# FIT_HDMI_X16-33.net
KiCad netlist of a schematic drawn in Altium Designer
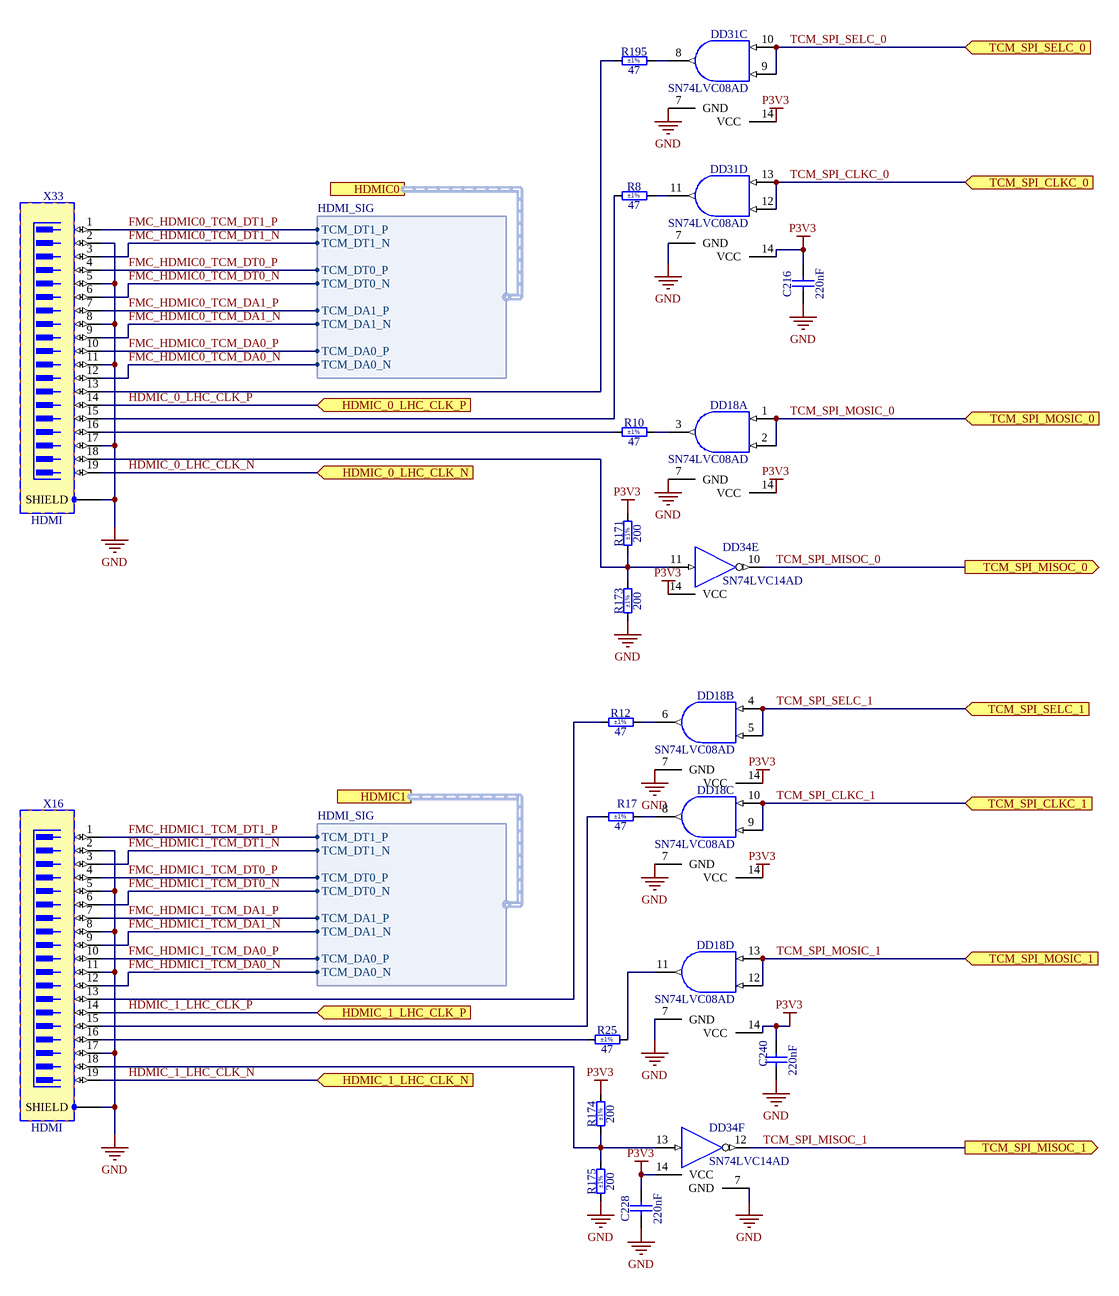
[diagram p0: FIT_HDMI_X16-33.SchDoc]

(export (version "E")
  (design (tool "Eeschema 10.0.6"))
  (components
    (comp (ref "C216")
      (value "220nF")
      (footprint "CAPC2012X135N")
      (description "Non-polarised capacitor")
      (fields
        (field (name "PART NUMBER") "CC0805_220NF_50V_10%_X7R")
        (field (name "VOLTAGE") "50V")
        (field (name "AUTHOR") "CERN DEM JLC")
      )
      (libsource (lib "Capacitors") (part "Capacitor - non polarized"))
    )
    (comp (ref "C228")
      (value "220nF")
      (footprint "CAPC2012X135N")
      (description "Non-polarised capacitor")
      (fields
        (field (name "PART NUMBER") "CC0805_220NF_50V_10%_X7R")
        (field (name "VOLTAGE") "50V")
        (field (name "AUTHOR") "CERN DEM JLC")
      )
      (libsource (lib "Capacitors") (part "Capacitor - non polarized"))
    )
    (comp (ref "C240")
      (value "220nF")
      (footprint "CAPC2012X135N")
      (description "Non-polarised capacitor")
      (fields
        (field (name "PART NUMBER") "CC0805_220NF_50V_10%_X7R")
        (field (name "VOLTAGE") "50V")
        (field (name "AUTHOR") "CERN DEM JLC")
      )
      (libsource (lib "Capacitors") (part "Capacitor - non polarized"))
    )
    (comp (ref "DD18")
      (value "SN74LVC08AD")
      (footprint "SOIC127P600X175-14N")
      (description "Quad 2-Input AND Gate")
      (fields (field (name "MANUFACTURER") "TEXAS INSTRUMENTS") (field (name "AUTHOR") "CERN DEM JLC"))
      (libsource (lib "ICs And Semiconductors") (part "7408"))
    )
    (comp (ref "DD31")
      (value "SN74LVC08AD")
      (footprint "SOIC127P600X175-14N")
      (description "Quad 2-Input AND Gate")
      (fields (field (name "MANUFACTURER") "TEXAS INSTRUMENTS") (field (name "AUTHOR") "CERN DEM JLC"))
      (libsource (lib "ICs And Semiconductors") (part "7408"))
    )
    (comp (ref "DD34")
      (value "SN74LVC14AD")
      (footprint "SOIC127P600X175-14N")
      (description "Hex Schmitt-Trigger Inverter")
      (fields (field (name "MANUFACTURER") "TEXAS INSTRUMENTS") (field (name "AUTHOR") "CERN DEM JMW"))
      (libsource (lib "ICs And Semiconductors") (part "7414"))
    )
    (comp (ref "R8")
      (value "47")
      (footprint "RESC2012X60N")
      (description "Resistor - 1%")
      (fields
        (field (name "TOLERANCE") "±1%")
        (field (name "PART NUMBER") "R0805_47R_1%_0.125W_100PPM")
        (field (name "POWER") "0.125W")
        (field (name "AUTHOR") "CERN DEM JLC")
      )
      (libsource (lib "Resistors") (part "Resistor - 1%"))
    )
    (comp (ref "R10")
      (value "47")
      (footprint "RESC2012X60N")
      (description "Resistor - 1%")
      (fields
        (field (name "TOLERANCE") "±1%")
        (field (name "PART NUMBER") "R0805_47R_1%_0.125W_100PPM")
        (field (name "POWER") "0.125W")
        (field (name "AUTHOR") "CERN DEM JLC")
      )
      (libsource (lib "Resistors") (part "Resistor - 1%"))
    )
    (comp (ref "R12")
      (value "47")
      (footprint "RESC2012X60N")
      (description "Resistor - 1%")
      (fields
        (field (name "TOLERANCE") "±1%")
        (field (name "PART NUMBER") "R0805_47R_1%_0.125W_100PPM")
        (field (name "POWER") "0.125W")
        (field (name "AUTHOR") "CERN DEM JLC")
      )
      (libsource (lib "Resistors") (part "Resistor - 1%"))
    )
    (comp (ref "R17")
      (value "47")
      (footprint "RESC2012X60N")
      (description "Resistor - 1%")
      (fields
        (field (name "TOLERANCE") "±1%")
        (field (name "PART NUMBER") "R0805_47R_1%_0.125W_100PPM")
        (field (name "POWER") "0.125W")
        (field (name "AUTHOR") "CERN DEM JLC")
      )
      (libsource (lib "Resistors") (part "Resistor - 1%"))
    )
    (comp (ref "R25")
      (value "47")
      (footprint "RESC2012X60N")
      (description "Resistor - 1%")
      (fields
        (field (name "TOLERANCE") "±1%")
        (field (name "PART NUMBER") "R0805_47R_1%_0.125W_100PPM")
        (field (name "POWER") "0.125W")
        (field (name "AUTHOR") "CERN DEM JLC")
      )
      (libsource (lib "Resistors") (part "Resistor - 1%"))
    )
    (comp (ref "R171")
      (value "200")
      (footprint "RESC2012X60N")
      (description "Resistor - 1%")
      (fields
        (field (name "TOLERANCE") "±1%")
        (field (name "PART NUMBER") "R0805_200R_1%_0.125W_100PPM")
        (field (name "POWER") "0.125W")
        (field (name "AUTHOR") "CERN DEM JLC")
      )
      (libsource (lib "Resistors") (part "Resistor - 1%"))
    )
    (comp (ref "R173")
      (value "200")
      (footprint "RESC2012X60N")
      (description "Resistor - 1%")
      (fields
        (field (name "TOLERANCE") "±1%")
        (field (name "PART NUMBER") "R0805_200R_1%_0.125W_100PPM")
        (field (name "POWER") "0.125W")
        (field (name "AUTHOR") "CERN DEM JLC")
      )
      (libsource (lib "Resistors") (part "Resistor - 1%"))
    )
    (comp (ref "R174")
      (value "200")
      (footprint "RESC2012X60N")
      (description "Resistor - 1%")
      (fields
        (field (name "TOLERANCE") "±1%")
        (field (name "PART NUMBER") "R0805_200R_1%_0.125W_100PPM")
        (field (name "POWER") "0.125W")
        (field (name "AUTHOR") "CERN DEM JLC")
      )
      (libsource (lib "Resistors") (part "Resistor - 1%"))
    )
    (comp (ref "R175")
      (value "200")
      (footprint "RESC2012X60N")
      (description "Resistor - 1%")
      (fields
        (field (name "TOLERANCE") "±1%")
        (field (name "PART NUMBER") "R0805_200R_1%_0.125W_100PPM")
        (field (name "POWER") "0.125W")
        (field (name "AUTHOR") "CERN DEM JLC")
      )
      (libsource (lib "Resistors") (part "Resistor - 1%"))
    )
    (comp (ref "R195")
      (value "47")
      (footprint "RESC2012X60N")
      (description "Resistor - 1%")
      (fields
        (field (name "TOLERANCE") "±1%")
        (field (name "PART NUMBER") "R0805_47R_1%_0.125W_100PPM")
        (field (name "POWER") "0.125W")
        (field (name "AUTHOR") "CERN DEM JLC")
      )
      (libsource (lib "Resistors") (part "Resistor - 1%"))
    )
    (comp (ref "X16")
      (value "HDMI")
      (footprint "TYCO_2007435-1")
      (description "Connector HDMI 19 Male + 1 Shield")
      (fields
        (field (name "PART NUMBER") "TYCO_2007435-1")
        (field (name "MANUFACTURER") "TYCO ELECTRONICS")
        (field (name "AUTHOR") "CERN DEM MR")
      )
      (libsource (lib "Connectors") (part "Connector HDMI 19 Male + 1 Shield"))
    )
    (comp (ref "X33")
      (value "HDMI")
      (footprint "TYCO_2007435-1")
      (description "Connector HDMI 19 Male + 1 Shield")
      (fields
        (field (name "PART NUMBER") "TYCO_2007435-1")
        (field (name "MANUFACTURER") "TYCO ELECTRONICS")
        (field (name "AUTHOR") "CERN DEM MR")
      )
      (libsource (lib "Connectors") (part "Connector HDMI 19 Male + 1 Shield"))
    )
  )
  (nets
    (net (code "2") (name "/FMC_HDMIC0_TCM_DA0_N") (class "Default")
      (node (ref "X33") (pin "12") (pinfunction "12_12") (pintype "bidirectional"))
    )
    (net (code "3") (name "/FMC_HDMIC0_TCM_DA0_P") (class "Default")
      (node (ref "X33") (pin "10") (pinfunction "10_10") (pintype "bidirectional"))
    )
    (net (code "4") (name "/FMC_HDMIC0_TCM_DA1_N") (class "Default")
      (node (ref "X33") (pin "9") (pinfunction "9_9") (pintype "bidirectional"))
    )
    (net (code "5") (name "/FMC_HDMIC0_TCM_DA1_P") (class "Default")
      (node (ref "X33") (pin "7") (pinfunction "7_7") (pintype "bidirectional"))
    )
    (net (code "6") (name "/FMC_HDMIC0_TCM_DT0_N") (class "Default")
      (node (ref "X33") (pin "6") (pinfunction "6_6") (pintype "bidirectional"))
    )
    (net (code "7") (name "/FMC_HDMIC0_TCM_DT0_P") (class "Default")
      (node (ref "X33") (pin "4") (pinfunction "4_4") (pintype "bidirectional"))
    )
    (net (code "8") (name "/FMC_HDMIC0_TCM_DT1_N") (class "Default")
      (node (ref "X33") (pin "3") (pinfunction "3_3") (pintype "bidirectional"))
    )
    (net (code "9") (name "/FMC_HDMIC0_TCM_DT1_P") (class "Default")
      (node (ref "X33") (pin "1") (pinfunction "1_1") (pintype "bidirectional"))
    )
    (net (code "10") (name "/FMC_HDMIC1_TCM_DA0_N") (class "Default")
      (node (ref "X16") (pin "12") (pinfunction "12_12") (pintype "bidirectional"))
    )
    (net (code "11") (name "/FMC_HDMIC1_TCM_DA0_P") (class "Default")
      (node (ref "X16") (pin "10") (pinfunction "10_10") (pintype "bidirectional"))
    )
    (net (code "12") (name "/FMC_HDMIC1_TCM_DA1_N") (class "Default")
      (node (ref "X16") (pin "9") (pinfunction "9_9") (pintype "bidirectional"))
    )
    (net (code "13") (name "/FMC_HDMIC1_TCM_DA1_P") (class "Default")
      (node (ref "X16") (pin "7") (pinfunction "7_7") (pintype "bidirectional"))
    )
    (net (code "14") (name "/FMC_HDMIC1_TCM_DT0_N") (class "Default")
      (node (ref "X16") (pin "6") (pinfunction "6_6") (pintype "bidirectional"))
    )
    (net (code "15") (name "/FMC_HDMIC1_TCM_DT0_P") (class "Default")
      (node (ref "X16") (pin "4") (pinfunction "4_4") (pintype "bidirectional"))
    )
    (net (code "16") (name "/FMC_HDMIC1_TCM_DT1_N") (class "Default")
      (node (ref "X16") (pin "3") (pinfunction "3_3") (pintype "bidirectional"))
    )
    (net (code "17") (name "/FMC_HDMIC1_TCM_DT1_P") (class "Default")
      (node (ref "X16") (pin "1") (pinfunction "1_1") (pintype "bidirectional"))
    )
    (net (code "18") (name "/HDMIC_0_LHC_CLK_N") (class "Default")
      (node (ref "X33") (pin "19") (pinfunction "19_19") (pintype "bidirectional"))
    )
    (net (code "19") (name "/HDMIC_0_LHC_CLK_P") (class "Default")
      (node (ref "X33") (pin "14") (pinfunction "14_14") (pintype "bidirectional"))
    )
    (net (code "20") (name "/HDMIC_1_LHC_CLK_N") (class "Default")
      (node (ref "X16") (pin "19") (pinfunction "19_19") (pintype "bidirectional"))
    )
    (net (code "21") (name "/HDMIC_1_LHC_CLK_P") (class "Default")
      (node (ref "X16") (pin "14") (pinfunction "14_14") (pintype "bidirectional"))
    )
    (net (code "22") (name "/TCM_SPI_CLKC_0") (class "Default")
      (node (ref "DD31") (pin "12") (pinfunction "B_12") (pintype "input"))
      (node (ref "DD31") (pin "13") (pinfunction "A_13") (pintype "input"))
    )
    (net (code "23") (name "/TCM_SPI_CLKC_1") (class "Default")
      (node (ref "DD18") (pin "10") (pinfunction "A_10") (pintype "input"))
      (node (ref "DD18") (pin "9") (pinfunction "B_9") (pintype "input"))
    )
    (net (code "24") (name "/TCM_SPI_MISOC_0") (class "Default")
      (node (ref "DD34") (pin "10") (pinfunction "OUT_10") (pintype "output"))
    )
    (net (code "25") (name "/TCM_SPI_MISOC_1") (class "Default")
      (node (ref "DD34") (pin "12") (pinfunction "OUT_12") (pintype "output"))
    )
    (net (code "26") (name "/TCM_SPI_MOSIC_0") (class "Default")
      (node (ref "DD18") (pin "1") (pinfunction "A_1") (pintype "input"))
      (node (ref "DD18") (pin "2") (pinfunction "B_2") (pintype "input"))
    )
    (net (code "27") (name "/TCM_SPI_MOSIC_1") (class "Default")
      (node (ref "DD18") (pin "12") (pinfunction "B_12") (pintype "input"))
      (node (ref "DD18") (pin "13") (pinfunction "A_13") (pintype "input"))
    )
    (net (code "28") (name "/TCM_SPI_SELC_0") (class "Default")
      (node (ref "DD31") (pin "10") (pinfunction "A_10") (pintype "input"))
      (node (ref "DD31") (pin "9") (pinfunction "B_9") (pintype "input"))
    )
    (net (code "29") (name "/TCM_SPI_SELC_1") (class "Default")
      (node (ref "DD18") (pin "4") (pinfunction "A_4") (pintype "input"))
      (node (ref "DD18") (pin "5") (pinfunction "B_5") (pintype "input"))
    )
    (net (code "31") (name "GND") (class "Default")
      (node (ref "C216") (pin "1") (pinfunction "1_1") (pintype "passive"))
      (node (ref "C228") (pin "1") (pinfunction "1_1") (pintype "passive"))
      (node (ref "C240") (pin "1") (pinfunction "1_1") (pintype "passive"))
      (node (ref "DD18") (pin "7") (pinfunction "GND_7") (pintype "power_in"))
      (node (ref "DD31") (pin "7") (pinfunction "GND_7") (pintype "power_in"))
      (node (ref "DD34") (pin "7") (pinfunction "GND_7") (pintype "power_in"))
      (node (ref "R173") (pin "1") (pinfunction "1_1") (pintype "passive"))
      (node (ref "R175") (pin "1") (pinfunction "1_1") (pintype "passive"))
      (node (ref "X16") (pin "11") (pinfunction "11_11") (pintype "bidirectional"))
      (node (ref "X16") (pin "17") (pinfunction "17_17") (pintype "bidirectional"))
      (node (ref "X16") (pin "2") (pinfunction "2_2") (pintype "bidirectional"))
      (node (ref "X16") (pin "5") (pinfunction "5_5") (pintype "bidirectional"))
      (node (ref "X16") (pin "8") (pinfunction "8_8") (pintype "bidirectional"))
      (node (ref "X16") (pin "SHIELD") (pinfunction "SHIELD_SHIELD") (pintype "power_in"))
      (node (ref "X33") (pin "11") (pinfunction "11_11") (pintype "bidirectional"))
      (node (ref "X33") (pin "17") (pinfunction "17_17") (pintype "bidirectional"))
      (node (ref "X33") (pin "2") (pinfunction "2_2") (pintype "bidirectional"))
      (node (ref "X33") (pin "5") (pinfunction "5_5") (pintype "bidirectional"))
      (node (ref "X33") (pin "8") (pinfunction "8_8") (pintype "bidirectional"))
      (node (ref "X33") (pin "SHIELD") (pinfunction "SHIELD_SHIELD") (pintype "power_in"))
    )
    (net (code "32") (name "Net-(DD18A-Y)") (class "Default")
      (node (ref "DD18") (pin "3") (pinfunction "Y_3") (pintype "output"))
      (node (ref "R10") (pin "2") (pinfunction "2_2") (pintype "passive"))
    )
    (net (code "33") (name "Net-(DD18B-Y)") (class "Default")
      (node (ref "DD18") (pin "6") (pinfunction "Y_6") (pintype "output"))
      (node (ref "R12") (pin "2") (pinfunction "2_2") (pintype "passive"))
    )
    (net (code "34") (name "Net-(DD18C-Y)") (class "Default")
      (node (ref "DD18") (pin "8") (pinfunction "Y_8") (pintype "output"))
      (node (ref "R17") (pin "2") (pinfunction "2_2") (pintype "passive"))
    )
    (net (code "35") (name "Net-(DD18D-Y)") (class "Default")
      (node (ref "DD18") (pin "11") (pinfunction "Y_11") (pintype "output"))
      (node (ref "R25") (pin "2") (pinfunction "2_2") (pintype "passive"))
    )
    (net (code "36") (name "Net-(DD31C-Y)") (class "Default")
      (node (ref "DD31") (pin "8") (pinfunction "Y_8") (pintype "output"))
      (node (ref "R195") (pin "2") (pinfunction "2_2") (pintype "passive"))
    )
    (net (code "37") (name "Net-(DD31D-Y)") (class "Default")
      (node (ref "DD31") (pin "11") (pinfunction "Y_11") (pintype "output"))
      (node (ref "R8") (pin "2") (pinfunction "2_2") (pintype "passive"))
    )
    (net (code "38") (name "Net-(DD34E-IN)") (class "Default")
      (node (ref "DD34") (pin "11") (pinfunction "IN_11") (pintype "input"))
      (node (ref "R171") (pin "1") (pinfunction "1_1") (pintype "passive"))
      (node (ref "R173") (pin "2") (pinfunction "2_2") (pintype "passive"))
      (node (ref "X33") (pin "18") (pinfunction "18_18") (pintype "bidirectional"))
    )
    (net (code "39") (name "Net-(DD34F-IN)") (class "Default")
      (node (ref "DD34") (pin "13") (pinfunction "IN_13") (pintype "input"))
      (node (ref "R174") (pin "1") (pinfunction "1_1") (pintype "passive"))
      (node (ref "R175") (pin "2") (pinfunction "2_2") (pintype "passive"))
      (node (ref "X16") (pin "18") (pinfunction "18_18") (pintype "bidirectional"))
    )
    (net (code "40") (name "Net-(R8-Pad1)") (class "Default")
      (node (ref "R8") (pin "1") (pinfunction "1_1") (pintype "passive"))
      (node (ref "X33") (pin "15") (pinfunction "15_15") (pintype "bidirectional"))
    )
    (net (code "41") (name "Net-(R10-Pad1)") (class "Default")
      (node (ref "R10") (pin "1") (pinfunction "1_1") (pintype "passive"))
      (node (ref "X33") (pin "16") (pinfunction "16_16") (pintype "bidirectional"))
    )
    (net (code "42") (name "Net-(R12-Pad1)") (class "Default")
      (node (ref "R12") (pin "1") (pinfunction "1_1") (pintype "passive"))
      (node (ref "X16") (pin "13") (pinfunction "13_13") (pintype "bidirectional"))
    )
    (net (code "43") (name "Net-(R17-Pad1)") (class "Default")
      (node (ref "R17") (pin "1") (pinfunction "1_1") (pintype "passive"))
      (node (ref "X16") (pin "15") (pinfunction "15_15") (pintype "bidirectional"))
    )
    (net (code "44") (name "Net-(R25-Pad1)") (class "Default")
      (node (ref "R25") (pin "1") (pinfunction "1_1") (pintype "passive"))
      (node (ref "X16") (pin "16") (pinfunction "16_16") (pintype "bidirectional"))
    )
    (net (code "45") (name "Net-(R195-Pad1)") (class "Default")
      (node (ref "R195") (pin "1") (pinfunction "1_1") (pintype "passive"))
      (node (ref "X33") (pin "13") (pinfunction "13_13") (pintype "bidirectional"))
    )
    (net (code "46") (name "P3V3") (class "Default")
      (node (ref "C216") (pin "2") (pinfunction "2_2") (pintype "passive"))
      (node (ref "C228") (pin "2") (pinfunction "2_2") (pintype "passive"))
      (node (ref "C240") (pin "2") (pinfunction "2_2") (pintype "passive"))
      (node (ref "DD18") (pin "14") (pinfunction "VCC_14") (pintype "power_in"))
      (node (ref "DD31") (pin "14") (pinfunction "VCC_14") (pintype "power_in"))
      (node (ref "DD34") (pin "14") (pinfunction "VCC_14") (pintype "power_in"))
      (node (ref "R171") (pin "2") (pinfunction "2_2") (pintype "passive"))
      (node (ref "R174") (pin "2") (pinfunction "2_2") (pintype "passive"))
    )
  )
)
